# core-debug.net
KiCad netlist of a schematic drawn in EAGLE
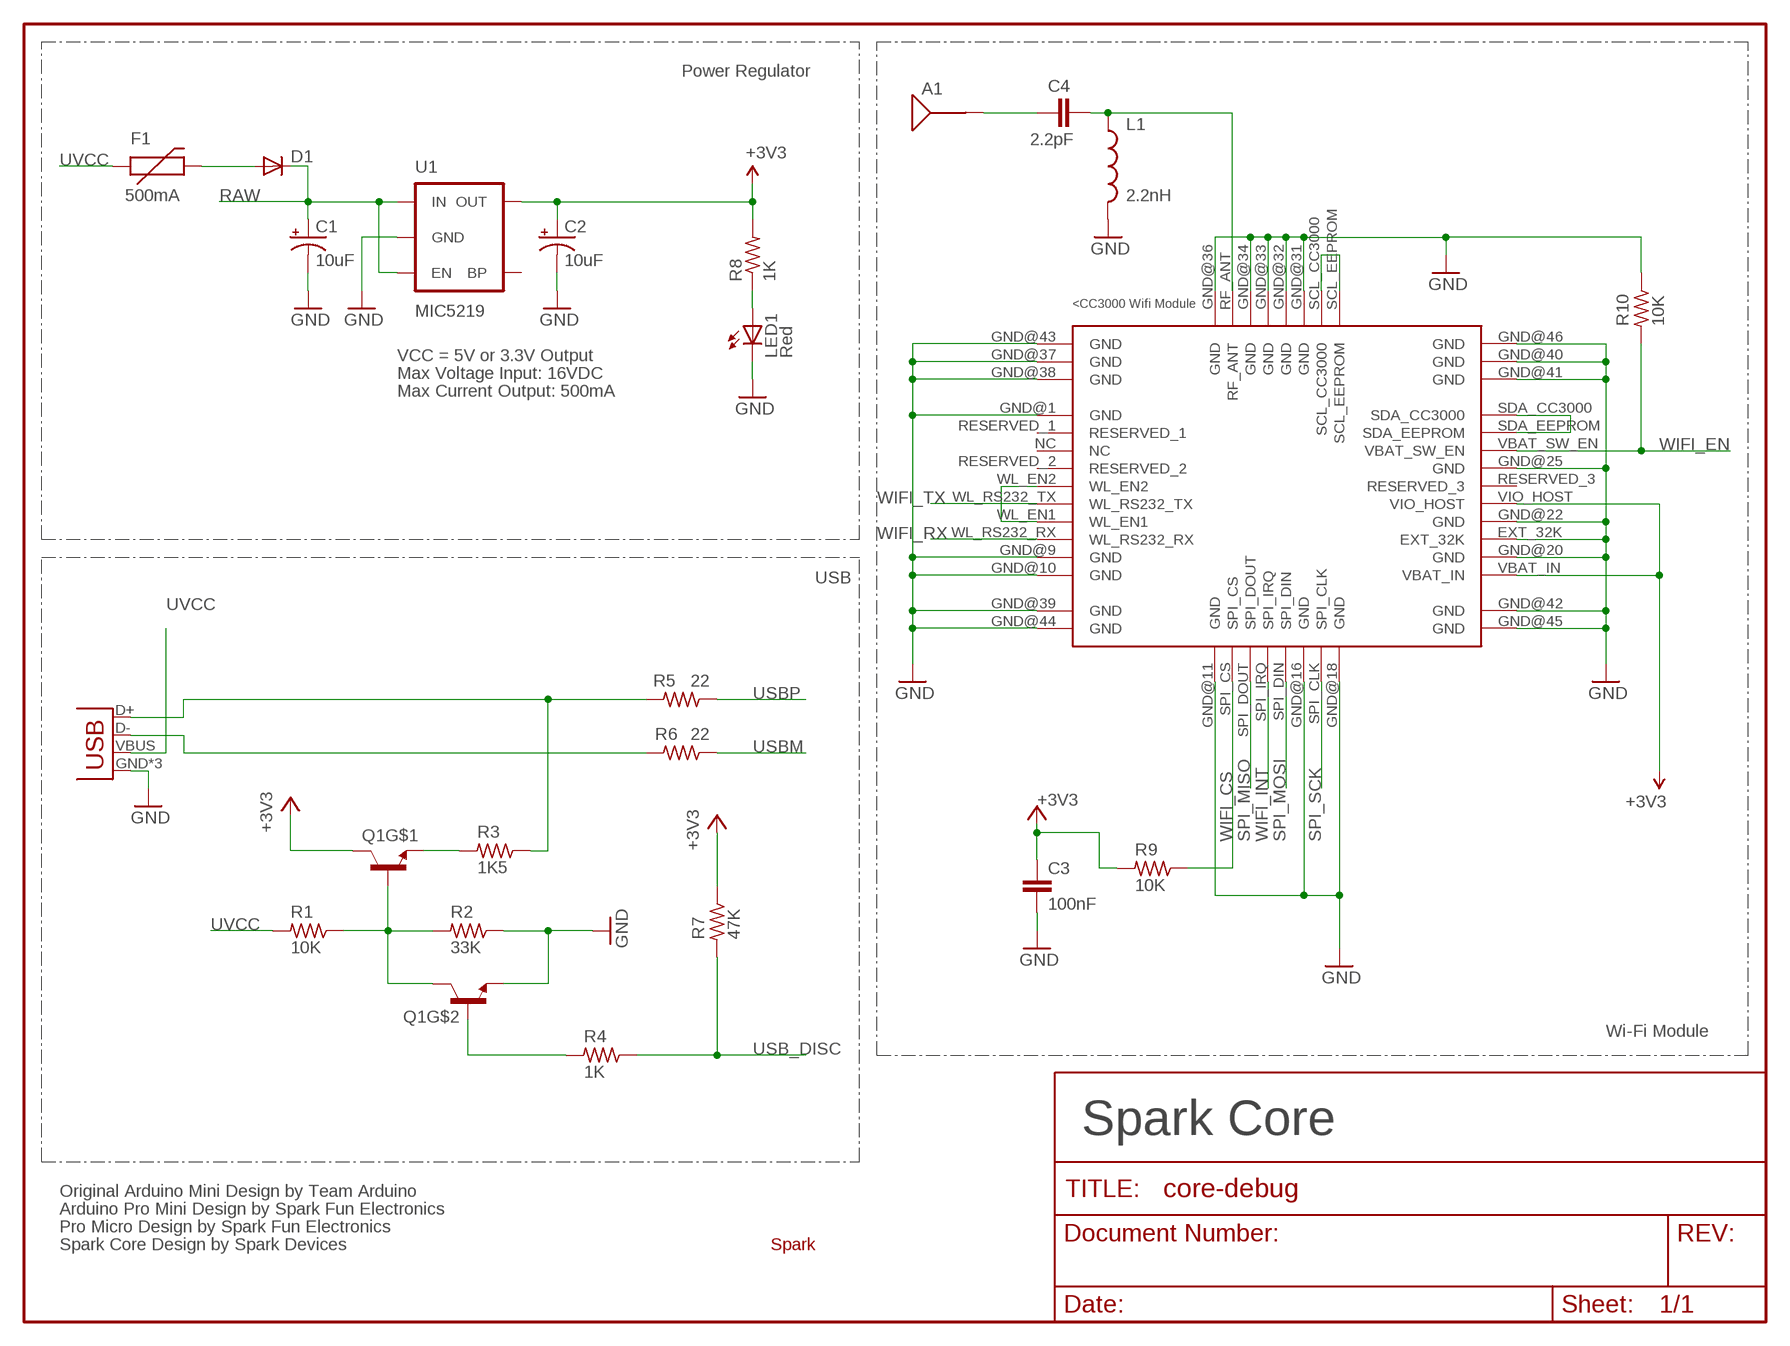
[diagram p0: schematic, sheet 1, part 1 of 2]
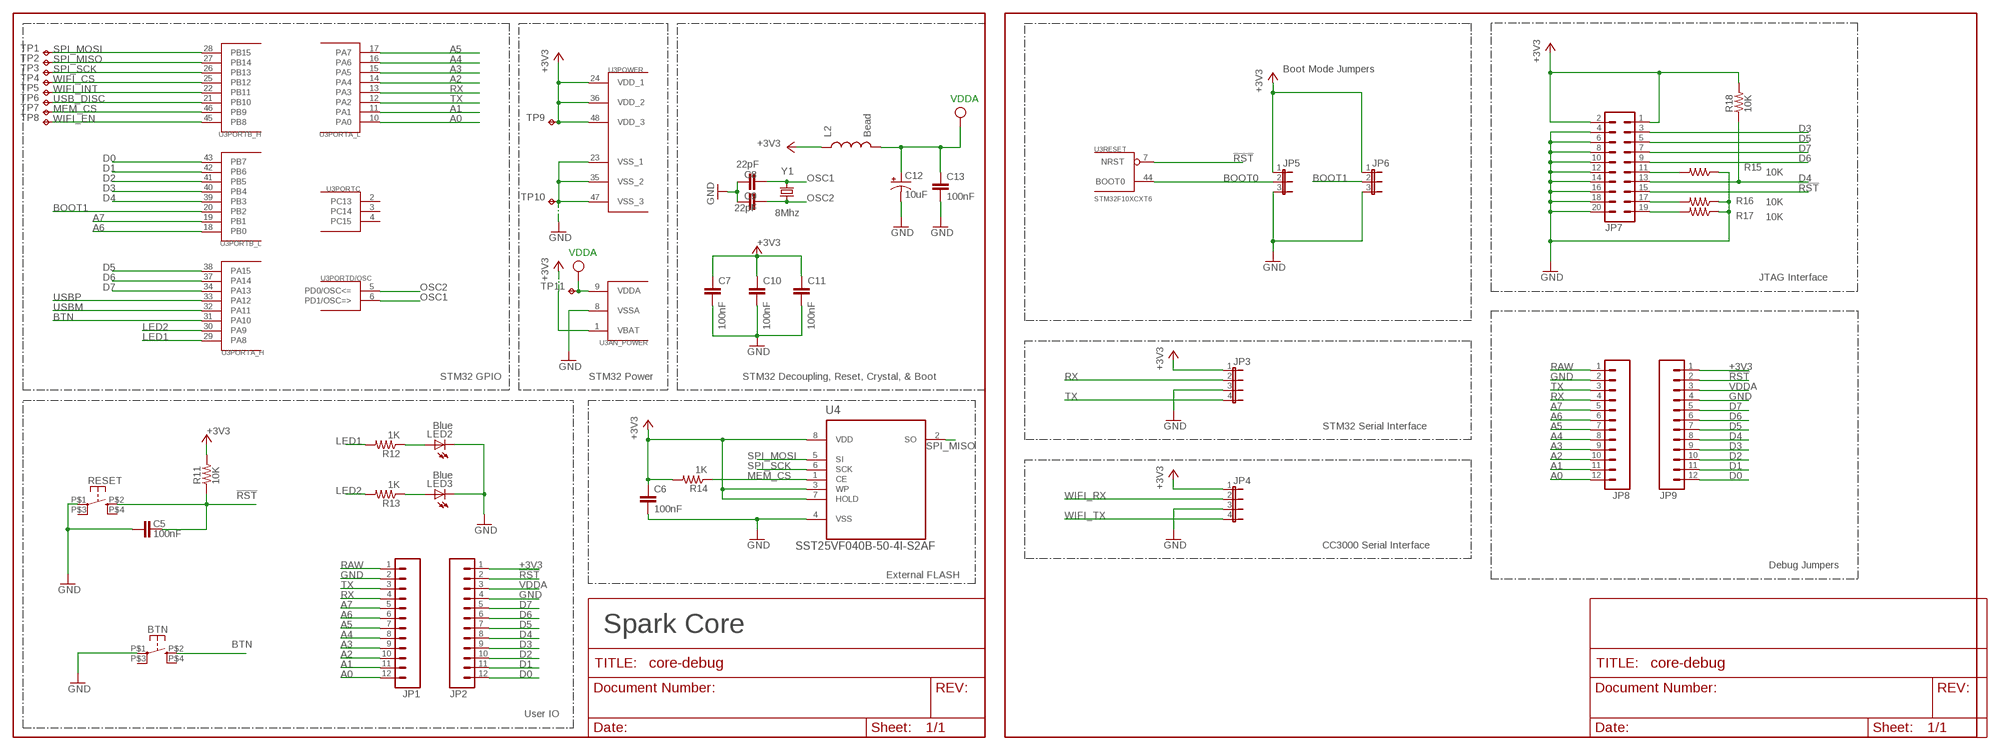
[diagram p1: schematic, sheet 1, part 2 of 2]

(export (version "E")
  (design (tool "Eeschema 10.0.6"))
  (components
    (comp (ref "A1")
      (value "ANTENNA2SMD5")
      (footprint "eagle-import:ANTENNA-CHIP5")
      (libsource (lib "eagle-import") (part "ANTENNA2SMD5"))
    )
    (comp (ref "BTN")
      (value "KMR211GLFS")
      (footprint "eagle-import:PUSHBUTTON-KMR241GLFS")
      (libsource (lib "eagle-import") (part "BUTTON-KMR241GLFS"))
    )
    (comp (ref "C1")
      (value "10uF")
      (footprint "eagle-import:EIA3216")
      (libsource (lib "eagle-import") (part "CAP_POL1206"))
    )
    (comp (ref "C2")
      (value "10uF")
      (footprint "eagle-import:EIA3216")
      (libsource (lib "eagle-import") (part "CAP_POL1206"))
    )
    (comp (ref "C3")
      (value "100nF")
      (footprint "eagle-import:C0603")
      (libsource (lib "eagle-import") (part "C-EUC0603"))
    )
    (comp (ref "C4")
      (value "2.2pF")
      (footprint "eagle-import:C0603")
      (libsource (lib "eagle-import") (part "C-EUC0603"))
    )
    (comp (ref "C5")
      (value "100nF")
      (footprint "eagle-import:C0603")
      (libsource (lib "eagle-import") (part "C-EUC0603"))
    )
    (comp (ref "C6")
      (value "100nF")
      (footprint "eagle-import:C0603")
      (libsource (lib "eagle-import") (part "C-EUC0603"))
    )
    (comp (ref "C7")
      (value "100nF")
      (footprint "eagle-import:C0603")
      (libsource (lib "eagle-import") (part "C-EUC0603"))
    )
    (comp (ref "C8")
      (value "22pF")
      (footprint "eagle-import:C0603")
      (libsource (lib "eagle-import") (part "C-EUC0603"))
    )
    (comp (ref "C9")
      (value "22pF")
      (footprint "eagle-import:C0603")
      (libsource (lib "eagle-import") (part "C-EUC0603"))
    )
    (comp (ref "C10")
      (value "100nF")
      (footprint "eagle-import:C0603")
      (libsource (lib "eagle-import") (part "C-EUC0603"))
    )
    (comp (ref "C11")
      (value "100nF")
      (footprint "eagle-import:C0603")
      (libsource (lib "eagle-import") (part "C-EUC0603"))
    )
    (comp (ref "C12")
      (value "10uF")
      (footprint "eagle-import:EIA3216")
      (libsource (lib "eagle-import") (part "CAP_POL1206"))
    )
    (comp (ref "C13")
      (value "100nF")
      (footprint "eagle-import:C0603")
      (libsource (lib "eagle-import") (part "C-EUC0603"))
    )
    (comp (ref "D1")
      (value "DIODESOD")
      (footprint "eagle-import:SOD-323")
      (libsource (lib "eagle-import") (part "DIODESOD"))
    )
    (comp (ref "F1")
      (value "500mA")
      (footprint "eagle-import:PTC-1206")
      (libsource (lib "eagle-import") (part "PTCSMD"))
    )
    (comp (ref "JP1")
      (value "M12PTH")
      (footprint "eagle-import:1X12")
      (libsource (lib "eagle-import") (part "M12PTH"))
    )
    (comp (ref "JP2")
      (value "M12PTH")
      (footprint "eagle-import:1X12")
      (libsource (lib "eagle-import") (part "M12PTH"))
    )
    (comp (ref "JP3")
      (value "JP4E")
      (footprint "eagle-import:JP4")
      (libsource (lib "eagle-import") (part "JP4E"))
    )
    (comp (ref "JP4")
      (value "JP4E")
      (footprint "eagle-import:JP4")
      (libsource (lib "eagle-import") (part "JP4E"))
    )
    (comp (ref "JP5")
      (value "JP2E")
      (footprint "eagle-import:JP2")
      (libsource (lib "eagle-import") (part "JP2E"))
    )
    (comp (ref "JP6")
      (value "JP2E")
      (footprint "eagle-import:JP2")
      (libsource (lib "eagle-import") (part "JP2E"))
    )
    (comp (ref "JP7")
      (value "ML20")
      (footprint "eagle-import:ML20")
      (libsource (lib "eagle-import") (part "ML20"))
    )
    (comp (ref "JP8")
      (value "M12PTH")
      (footprint "eagle-import:1X12")
      (libsource (lib "eagle-import") (part "M12PTH"))
    )
    (comp (ref "JP9")
      (value "M12PTH")
      (footprint "eagle-import:1X12")
      (libsource (lib "eagle-import") (part "M12PTH"))
    )
    (comp (ref "L1")
      (value "2.2nH")
      (footprint "eagle-import:0603")
      (libsource (lib "eagle-import") (part "INDUCTOR0603"))
    )
    (comp (ref "L2")
      (value "Bead")
      (footprint "eagle-import:0603")
      (libsource (lib "eagle-import") (part "INDUCTOR0603"))
    )
    (comp (ref "LED1")
      (value "Red")
      (footprint "eagle-import:LED-0603")
      (libsource (lib "eagle-import") (part "LED0603"))
    )
    (comp (ref "LED2")
      (value "Blue")
      (footprint "eagle-import:LED-0603")
      (libsource (lib "eagle-import") (part "LED0603"))
    )
    (comp (ref "LED3")
      (value "Blue")
      (footprint "eagle-import:LED-0603")
      (libsource (lib "eagle-import") (part "LED0603"))
    )
    (comp (ref "Q1")
      (value "MMDT3904")
      (footprint "eagle-import:SOT363")
      (libsource (lib "eagle-import") (part "MMDT3904"))
    )
    (comp (ref "R1")
      (value "10K")
      (footprint "eagle-import:R0603")
      (libsource (lib "eagle-import") (part "R-US_R0603"))
    )
    (comp (ref "R2")
      (value "33K")
      (footprint "eagle-import:R0603")
      (libsource (lib "eagle-import") (part "R-US_R0603"))
    )
    (comp (ref "R3")
      (value "1K5")
      (footprint "eagle-import:R0603")
      (libsource (lib "eagle-import") (part "R-US_R0603"))
    )
    (comp (ref "R4")
      (value "1K")
      (footprint "eagle-import:R0603")
      (libsource (lib "eagle-import") (part "R-US_R0603"))
    )
    (comp (ref "R5")
      (value "22")
      (footprint "eagle-import:R0603")
      (libsource (lib "eagle-import") (part "R-US_R0603"))
    )
    (comp (ref "R6")
      (value "22")
      (footprint "eagle-import:R0603")
      (libsource (lib "eagle-import") (part "R-US_R0603"))
    )
    (comp (ref "R7")
      (value "47K")
      (footprint "eagle-import:R0603")
      (libsource (lib "eagle-import") (part "R-US_R0603"))
    )
    (comp (ref "R8")
      (value "1K")
      (footprint "eagle-import:R0603")
      (libsource (lib "eagle-import") (part "R-US_R0603"))
    )
    (comp (ref "R9")
      (value "10K")
      (footprint "eagle-import:R0603")
      (libsource (lib "eagle-import") (part "R-US_R0603"))
    )
    (comp (ref "R10")
      (value "10K")
      (footprint "eagle-import:R0603")
      (libsource (lib "eagle-import") (part "R-US_R0603"))
    )
    (comp (ref "R11")
      (value "10K")
      (footprint "eagle-import:R0603")
      (libsource (lib "eagle-import") (part "R-US_R0603"))
    )
    (comp (ref "R12")
      (value "1K")
      (footprint "eagle-import:R0603")
      (libsource (lib "eagle-import") (part "R-US_R0603"))
    )
    (comp (ref "R13")
      (value "1K")
      (footprint "eagle-import:R0603")
      (libsource (lib "eagle-import") (part "R-US_R0603"))
    )
    (comp (ref "R14")
      (value "1K")
      (footprint "eagle-import:R0603")
      (libsource (lib "eagle-import") (part "R-US_R0603"))
    )
    (comp (ref "R15")
      (value "10K")
      (footprint "eagle-import:R0603")
      (libsource (lib "eagle-import") (part "R-US_R0603"))
    )
    (comp (ref "R16")
      (value "10K")
      (footprint "eagle-import:R0603")
      (libsource (lib "eagle-import") (part "R-US_R0603"))
    )
    (comp (ref "R17")
      (value "10K")
      (footprint "eagle-import:R0603")
      (libsource (lib "eagle-import") (part "R-US_R0603"))
    )
    (comp (ref "R18")
      (value "10K")
      (footprint "eagle-import:R0603")
      (libsource (lib "eagle-import") (part "R-US_R0603"))
    )
    (comp (ref "RESET")
      (value "KMR211GLFS")
      (footprint "eagle-import:PUSHBUTTON-KMR241GLFS")
      (libsource (lib "eagle-import") (part "BUTTON-KMR241GLFS"))
    )
    (comp (ref "TP1")
      (value "TPPAD1-17")
      (footprint "eagle-import:P1-17")
      (libsource (lib "eagle-import") (part "TPPAD1-17"))
    )
    (comp (ref "TP2")
      (value "TPPAD1-17")
      (footprint "eagle-import:P1-17")
      (libsource (lib "eagle-import") (part "TPPAD1-17"))
    )
    (comp (ref "TP3")
      (value "TPPAD1-17")
      (footprint "eagle-import:P1-17")
      (libsource (lib "eagle-import") (part "TPPAD1-17"))
    )
    (comp (ref "TP4")
      (value "TPPAD1-17")
      (footprint "eagle-import:P1-17")
      (libsource (lib "eagle-import") (part "TPPAD1-17"))
    )
    (comp (ref "TP5")
      (value "TPPAD1-17")
      (footprint "eagle-import:P1-17")
      (libsource (lib "eagle-import") (part "TPPAD1-17"))
    )
    (comp (ref "TP6")
      (value "TPPAD1-17")
      (footprint "eagle-import:P1-17")
      (libsource (lib "eagle-import") (part "TPPAD1-17"))
    )
    (comp (ref "TP7")
      (value "TPPAD1-17")
      (footprint "eagle-import:P1-17")
      (libsource (lib "eagle-import") (part "TPPAD1-17"))
    )
    (comp (ref "TP8")
      (value "TPPAD1-17")
      (footprint "eagle-import:P1-17")
      (libsource (lib "eagle-import") (part "TPPAD1-17"))
    )
    (comp (ref "TP9")
      (value "TPPAD1-17")
      (footprint "eagle-import:P1-17")
      (libsource (lib "eagle-import") (part "TPPAD1-17"))
    )
    (comp (ref "TP10")
      (value "TPPAD1-17")
      (footprint "eagle-import:P1-17")
      (libsource (lib "eagle-import") (part "TPPAD1-17"))
    )
    (comp (ref "TP11")
      (value "TPPAD1-17")
      (footprint "eagle-import:P1-17")
      (libsource (lib "eagle-import") (part "TPPAD1-17"))
    )
    (comp (ref "U$1")
      (value "SPARK_LOGO2")
      (footprint "eagle-import:SPARK_LOGO2")
      (libsource (lib "eagle-import") (part "SPARK_LOGO2"))
    )
    (comp (ref "U1")
      (value "MIC5219")
      (footprint "eagle-import:SOT23-5")
      (libsource (lib "eagle-import") (part "V_REG_LDOSMD"))
    )
    (comp (ref "U2")
      (value "CC3000")
      (footprint "eagle-import:CC3000")
      (libsource (lib "eagle-import") (part "CC3000"))
    )
    (comp (ref "U3")
      (value "STM32F10XCXT6")
      (footprint "eagle-import:TQFP48")
      (libsource (lib "eagle-import") (part "STM32F10XCXT6"))
    )
    (comp (ref "U4")
      (value "SST25VF040B-50-4I-S2AF")
      (footprint "eagle-import:SOIC127P790X216-8N")
      (libsource (lib "eagle-import") (part "SST25VF040B-50-4I-S2AF"))
    )
    (comp (ref "X1")
      (value "USB-MICROB")
      (footprint "eagle-import:USB-MICROB")
      (libsource (lib "eagle-import") (part "USB-MICROB"))
    )
    (comp (ref "Y1")
      (value "8Mhz")
      (footprint "eagle-import:CRYSTAL-SMD-5X3")
      (libsource (lib "eagle-import") (part "CRYSTAL5X3"))
    )
  )
  (nets
    (net (code "1") (name "+3V3") (class "Default")
      (node (ref "C10") (pin "1") (pinfunction "1_1") (pintype "passive"))
      (node (ref "C11") (pin "1") (pinfunction "1_1") (pintype "passive"))
      (node (ref "C2") (pin "A") (pinfunction "+_A") (pintype "passive"))
      (node (ref "C3") (pin "1") (pinfunction "1_1") (pintype "passive"))
      (node (ref "C6") (pin "1") (pinfunction "1_1") (pintype "passive"))
      (node (ref "C7") (pin "1") (pinfunction "1_1") (pintype "passive"))
      (node (ref "JP2") (pin "1") (pinfunction "1_1") (pintype "passive"))
      (node (ref "JP3") (pin "1") (pinfunction "1_1") (pintype "passive"))
      (node (ref "JP4") (pin "1") (pinfunction "1_1") (pintype "passive"))
      (node (ref "JP5") (pin "1") (pinfunction "1_1") (pintype "passive"))
      (node (ref "JP6") (pin "1") (pinfunction "1_1") (pintype "passive"))
      (node (ref "JP7") (pin "1") (pinfunction "1_1") (pintype "passive"))
      (node (ref "JP7") (pin "2") (pinfunction "2_2") (pintype "passive"))
      (node (ref "JP9") (pin "1") (pinfunction "1_1") (pintype "passive"))
      (node (ref "L2") (pin "1") (pinfunction "1_1") (pintype "passive"))
      (node (ref "Q1") (pin "3") (pinfunction "C_3") (pintype "passive"))
      (node (ref "R11") (pin "2") (pinfunction "2_2") (pintype "passive"))
      (node (ref "R14") (pin "2") (pinfunction "2_2") (pintype "passive"))
      (node (ref "R18") (pin "2") (pinfunction "2_2") (pintype "passive"))
      (node (ref "R7") (pin "1") (pinfunction "1_1") (pintype "passive"))
      (node (ref "R8") (pin "2") (pinfunction "2_2") (pintype "passive"))
      (node (ref "R9") (pin "2") (pinfunction "2_2") (pintype "passive"))
      (node (ref "TP9") (pin "TP") (pinfunction "TP_TP") (pintype "input"))
      (node (ref "U1") (pin "5") (pinfunction "OUT_5") (pintype "passive"))
      (node (ref "U2") (pin "VBAT_IN") (pinfunction "VBAT_IN_VBAT_IN") (pintype "power_in"))
      (node (ref "U2") (pin "VIO_HOST") (pinfunction "VIO_HOST_VIO_HOST") (pintype "power_in"))
      (node (ref "U3") (pin "1") (pinfunction "VBAT_1") (pintype "power_in"))
      (node (ref "U3") (pin "24") (pinfunction "VDD_1_24") (pintype "power_in"))
      (node (ref "U3") (pin "36") (pinfunction "VDD_2_36") (pintype "power_in"))
      (node (ref "U3") (pin "48") (pinfunction "VDD_3_48") (pintype "power_in"))
      (node (ref "U4") (pin "3") (pinfunction "WP_3") (pintype "input"))
      (node (ref "U4") (pin "7") (pinfunction "HOLD_7") (pintype "input"))
      (node (ref "U4") (pin "8") (pinfunction "VDD_8") (pintype "power_in"))
    )
    (net (code "2") (name "/A0") (class "Default")
      (node (ref "JP1") (pin "12") (pinfunction "12_12") (pintype "passive"))
      (node (ref "JP8") (pin "12") (pinfunction "12_12") (pintype "passive"))
      (node (ref "U3") (pin "10") (pinfunction "PA0_10") (pintype "bidirectional"))
    )
    (net (code "3") (name "/A1") (class "Default")
      (node (ref "JP1") (pin "11") (pinfunction "11_11") (pintype "passive"))
      (node (ref "JP8") (pin "11") (pinfunction "11_11") (pintype "passive"))
      (node (ref "U3") (pin "11") (pinfunction "PA1_11") (pintype "bidirectional"))
    )
    (net (code "4") (name "/A2") (class "Default")
      (node (ref "JP1") (pin "10") (pinfunction "10_10") (pintype "passive"))
      (node (ref "JP8") (pin "10") (pinfunction "10_10") (pintype "passive"))
      (node (ref "U3") (pin "14") (pinfunction "PA4_14") (pintype "bidirectional"))
    )
    (net (code "5") (name "/A3") (class "Default")
      (node (ref "JP1") (pin "9") (pinfunction "9_9") (pintype "passive"))
      (node (ref "JP8") (pin "9") (pinfunction "9_9") (pintype "passive"))
      (node (ref "U3") (pin "15") (pinfunction "PA5_15") (pintype "bidirectional"))
    )
    (net (code "6") (name "/A4") (class "Default")
      (node (ref "JP1") (pin "8") (pinfunction "8_8") (pintype "passive"))
      (node (ref "JP8") (pin "8") (pinfunction "8_8") (pintype "passive"))
      (node (ref "U3") (pin "16") (pinfunction "PA6_16") (pintype "bidirectional"))
    )
    (net (code "7") (name "/A5") (class "Default")
      (node (ref "JP1") (pin "7") (pinfunction "7_7") (pintype "passive"))
      (node (ref "JP8") (pin "7") (pinfunction "7_7") (pintype "passive"))
      (node (ref "U3") (pin "17") (pinfunction "PA7_17") (pintype "bidirectional"))
    )
    (net (code "8") (name "/A6") (class "Default")
      (node (ref "JP1") (pin "6") (pinfunction "6_6") (pintype "passive"))
      (node (ref "JP8") (pin "6") (pinfunction "6_6") (pintype "passive"))
      (node (ref "U3") (pin "18") (pinfunction "PB0_18") (pintype "bidirectional"))
    )
    (net (code "9") (name "/A7") (class "Default")
      (node (ref "JP1") (pin "5") (pinfunction "5_5") (pintype "passive"))
      (node (ref "JP8") (pin "5") (pinfunction "5_5") (pintype "passive"))
      (node (ref "U3") (pin "19") (pinfunction "PB1_19") (pintype "bidirectional"))
    )
    (net (code "10") (name "/BOOT0") (class "Default")
      (node (ref "JP5") (pin "2") (pinfunction "2_2") (pintype "passive"))
      (node (ref "U3") (pin "44") (pinfunction "BOOT0_44") (pintype "input"))
    )
    (net (code "11") (name "/BOOT1") (class "Default")
      (node (ref "JP6") (pin "2") (pinfunction "2_2") (pintype "passive"))
      (node (ref "U3") (pin "20") (pinfunction "PB2_20") (pintype "bidirectional"))
    )
    (net (code "12") (name "/BTN") (class "Default")
      (node (ref "BTN") (pin "P$2") (pinfunction "2_P$2") (pintype "passive"))
      (node (ref "U3") (pin "31") (pinfunction "PA10_31") (pintype "bidirectional"))
    )
    (net (code "13") (name "/D0") (class "Default")
      (node (ref "JP2") (pin "12") (pinfunction "12_12") (pintype "passive"))
      (node (ref "JP9") (pin "12") (pinfunction "12_12") (pintype "passive"))
      (node (ref "U3") (pin "43") (pinfunction "PB7_43") (pintype "bidirectional"))
    )
    (net (code "14") (name "/D1") (class "Default")
      (node (ref "JP2") (pin "11") (pinfunction "11_11") (pintype "passive"))
      (node (ref "JP9") (pin "11") (pinfunction "11_11") (pintype "passive"))
      (node (ref "U3") (pin "42") (pinfunction "PB6_42") (pintype "bidirectional"))
    )
    (net (code "15") (name "/D2") (class "Default")
      (node (ref "JP2") (pin "10") (pinfunction "10_10") (pintype "passive"))
      (node (ref "JP9") (pin "10") (pinfunction "10_10") (pintype "passive"))
      (node (ref "U3") (pin "41") (pinfunction "PB5_41") (pintype "bidirectional"))
    )
    (net (code "16") (name "/D3") (class "Default")
      (node (ref "JP2") (pin "9") (pinfunction "9_9") (pintype "passive"))
      (node (ref "JP7") (pin "3") (pinfunction "3_3") (pintype "passive"))
      (node (ref "JP9") (pin "9") (pinfunction "9_9") (pintype "passive"))
      (node (ref "U3") (pin "40") (pinfunction "PB4_40") (pintype "bidirectional"))
    )
    (net (code "17") (name "/D4") (class "Default")
      (node (ref "JP2") (pin "8") (pinfunction "8_8") (pintype "passive"))
      (node (ref "JP7") (pin "13") (pinfunction "13_13") (pintype "passive"))
      (node (ref "JP9") (pin "8") (pinfunction "8_8") (pintype "passive"))
      (node (ref "R18") (pin "1") (pinfunction "1_1") (pintype "passive"))
      (node (ref "U3") (pin "39") (pinfunction "PB3_39") (pintype "bidirectional"))
    )
    (net (code "18") (name "/D5") (class "Default")
      (node (ref "JP2") (pin "7") (pinfunction "7_7") (pintype "passive"))
      (node (ref "JP7") (pin "5") (pinfunction "5_5") (pintype "passive"))
      (node (ref "JP9") (pin "7") (pinfunction "7_7") (pintype "passive"))
      (node (ref "U3") (pin "38") (pinfunction "PA15_38") (pintype "bidirectional"))
    )
    (net (code "19") (name "/D6") (class "Default")
      (node (ref "JP2") (pin "6") (pinfunction "6_6") (pintype "passive"))
      (node (ref "JP7") (pin "9") (pinfunction "9_9") (pintype "passive"))
      (node (ref "JP9") (pin "6") (pinfunction "6_6") (pintype "passive"))
      (node (ref "U3") (pin "37") (pinfunction "PA14_37") (pintype "bidirectional"))
    )
    (net (code "20") (name "/D7") (class "Default")
      (node (ref "JP2") (pin "5") (pinfunction "5_5") (pintype "passive"))
      (node (ref "JP7") (pin "7") (pinfunction "7_7") (pintype "passive"))
      (node (ref "JP9") (pin "5") (pinfunction "5_5") (pintype "passive"))
      (node (ref "U3") (pin "34") (pinfunction "PA13_34") (pintype "bidirectional"))
    )
    (net (code "21") (name "/LED1") (class "Default")
      (node (ref "R12") (pin "2") (pinfunction "2_2") (pintype "passive"))
      (node (ref "U3") (pin "29") (pinfunction "PA8_29") (pintype "bidirectional"))
    )
    (net (code "22") (name "/LED2") (class "Default")
      (node (ref "R13") (pin "2") (pinfunction "2_2") (pintype "passive"))
      (node (ref "U3") (pin "30") (pinfunction "PA9_30") (pintype "bidirectional"))
    )
    (net (code "23") (name "/MEM_CS") (class "Default")
      (node (ref "R14") (pin "1") (pinfunction "1_1") (pintype "passive"))
      (node (ref "TP7") (pin "TP") (pinfunction "TP_TP") (pintype "input"))
      (node (ref "U3") (pin "46") (pinfunction "PB9_46") (pintype "bidirectional"))
      (node (ref "U4") (pin "1") (pinfunction "CE_1") (pintype "input"))
    )
    (net (code "24") (name "/OSC1") (class "Default")
      (node (ref "C8") (pin "1") (pinfunction "1_1") (pintype "passive"))
      (node (ref "U3") (pin "6") (pinfunction "PD1/OSC=>_6") (pintype "bidirectional"))
      (node (ref "Y1") (pin "3") (pinfunction "2_3") (pintype "passive"))
    )
    (net (code "25") (name "/OSC2") (class "Default")
      (node (ref "C9") (pin "1") (pinfunction "1_1") (pintype "passive"))
      (node (ref "U3") (pin "5") (pinfunction "PD0/OSC<=_5") (pintype "bidirectional"))
      (node (ref "Y1") (pin "1") (pinfunction "1_1") (pintype "passive"))
    )
    (net (code "26") (name "/RAW") (class "Default")
      (node (ref "C1") (pin "A") (pinfunction "+_A") (pintype "passive"))
      (node (ref "D1") (pin "1") (pinfunction "C_1") (pintype "passive"))
      (node (ref "JP1") (pin "1") (pinfunction "1_1") (pintype "passive"))
      (node (ref "JP8") (pin "1") (pinfunction "1_1") (pintype "passive"))
      (node (ref "U1") (pin "1") (pinfunction "IN_1") (pintype "input"))
      (node (ref "U1") (pin "3") (pinfunction "EN_3") (pintype "input"))
    )
    (net (code "27") (name "/RX") (class "Default")
      (node (ref "JP1") (pin "4") (pinfunction "4_4") (pintype "passive"))
      (node (ref "JP3") (pin "2") (pinfunction "2_2") (pintype "passive"))
      (node (ref "JP8") (pin "4") (pinfunction "4_4") (pintype "passive"))
      (node (ref "U3") (pin "13") (pinfunction "PA3_13") (pintype "bidirectional"))
    )
    (net (code "28") (name "/SPI_MISO") (class "Default")
      (node (ref "TP2") (pin "TP") (pinfunction "TP_TP") (pintype "input"))
      (node (ref "U2") (pin "SPI_DOUT") (pinfunction "SPI_DOUT_SPI_DOUT") (pintype "output"))
      (node (ref "U3") (pin "27") (pinfunction "PB14_27") (pintype "bidirectional"))
      (node (ref "U4") (pin "2") (pinfunction "SO_2") (pintype "output"))
    )
    (net (code "29") (name "/SPI_MOSI") (class "Default")
      (node (ref "TP1") (pin "TP") (pinfunction "TP_TP") (pintype "input"))
      (node (ref "U2") (pin "SPI_DIN") (pinfunction "SPI_DIN_SPI_DIN") (pintype "input"))
      (node (ref "U3") (pin "28") (pinfunction "PB15_28") (pintype "bidirectional"))
      (node (ref "U4") (pin "5") (pinfunction "SI_5") (pintype "input"))
    )
    (net (code "30") (name "/SPI_SCK") (class "Default")
      (node (ref "TP3") (pin "TP") (pinfunction "TP_TP") (pintype "input"))
      (node (ref "U2") (pin "SPI_CLK") (pinfunction "SPI_CLK_SPI_CLK") (pintype "input"))
      (node (ref "U3") (pin "26") (pinfunction "PB13_26") (pintype "bidirectional"))
      (node (ref "U4") (pin "6") (pinfunction "SCK_6") (pintype "input"))
    )
    (net (code "31") (name "/TX") (class "Default")
      (node (ref "JP1") (pin "3") (pinfunction "3_3") (pintype "passive"))
      (node (ref "JP3") (pin "4") (pinfunction "4_4") (pintype "passive"))
      (node (ref "JP8") (pin "3") (pinfunction "3_3") (pintype "passive"))
      (node (ref "U3") (pin "12") (pinfunction "PA2_12") (pintype "bidirectional"))
    )
    (net (code "32") (name "/USBM") (class "Default")
      (node (ref "R6") (pin "1") (pinfunction "1_1") (pintype "passive"))
      (node (ref "U3") (pin "32") (pinfunction "PA11_32") (pintype "bidirectional"))
    )
    (net (code "33") (name "/USBP") (class "Default")
      (node (ref "R5") (pin "1") (pinfunction "1_1") (pintype "passive"))
      (node (ref "U3") (pin "33") (pinfunction "PA12_33") (pintype "bidirectional"))
    )
    (net (code "34") (name "/USB_DISC") (class "Default")
      (node (ref "R4") (pin "1") (pinfunction "1_1") (pintype "passive"))
      (node (ref "R7") (pin "2") (pinfunction "2_2") (pintype "passive"))
      (node (ref "TP6") (pin "TP") (pinfunction "TP_TP") (pintype "input"))
      (node (ref "U3") (pin "21") (pinfunction "PB10_21") (pintype "bidirectional"))
    )
    (net (code "35") (name "/UVCC") (class "Default")
      (node (ref "F1") (pin "1") (pinfunction "1_1") (pintype "bidirectional"))
      (node (ref "R1") (pin "2") (pinfunction "2_2") (pintype "passive"))
      (node (ref "X1") (pin "VBUS") (pinfunction "VBUS_VBUS") (pintype "bidirectional"))
    )
    (net (code "36") (name "/WIFI_CS") (class "Default")
      (node (ref "R9") (pin "1") (pinfunction "1_1") (pintype "passive"))
      (node (ref "TP4") (pin "TP") (pinfunction "TP_TP") (pintype "input"))
      (node (ref "U2") (pin "SPI_CS") (pinfunction "SPI_CS_SPI_CS") (pintype "input"))
      (node (ref "U3") (pin "25") (pinfunction "PB12_25") (pintype "bidirectional"))
    )
    (net (code "37") (name "/WIFI_EN") (class "Default")
      (node (ref "R10") (pin "2") (pinfunction "2_2") (pintype "passive"))
      (node (ref "TP8") (pin "TP") (pinfunction "TP_TP") (pintype "input"))
      (node (ref "U2") (pin "VBAT_SW_EN") (pinfunction "VBAT_SW_EN_VBAT_SW_EN") (pintype "input"))
      (node (ref "U3") (pin "45") (pinfunction "PB8_45") (pintype "bidirectional"))
    )
    (net (code "38") (name "/WIFI_INT") (class "Default")
      (node (ref "TP5") (pin "TP") (pinfunction "TP_TP") (pintype "input"))
      (node (ref "U2") (pin "SPI_IRQ") (pinfunction "SPI_IRQ_SPI_IRQ") (pintype "output"))
      (node (ref "U3") (pin "22") (pinfunction "PB11_22") (pintype "bidirectional"))
    )
    (net (code "39") (name "/WIFI_RX") (class "Default")
      (node (ref "JP4") (pin "2") (pinfunction "2_2") (pintype "passive"))
      (node (ref "U2") (pin "WL_RS232_RX") (pinfunction "WL_RS232_RX_WL_RS232_RX") (pintype "input"))
    )
    (net (code "40") (name "/WIFI_TX") (class "Default")
      (node (ref "JP4") (pin "4") (pinfunction "4_4") (pintype "passive"))
      (node (ref "U2") (pin "WL_RS232_TX") (pinfunction "WL_RS232_TX_WL_RS232_TX") (pintype "output"))
    )
    (net (code "41") (name "/~{RST}") (class "Default")
      (node (ref "C5") (pin "2") (pinfunction "2_2") (pintype "passive"))
      (node (ref "JP2") (pin "2") (pinfunction "2_2") (pintype "passive"))
      (node (ref "JP7") (pin "15") (pinfunction "15_15") (pintype "passive"))
      (node (ref "JP9") (pin "2") (pinfunction "2_2") (pintype "passive"))
      (node (ref "R11") (pin "1") (pinfunction "1_1") (pintype "passive"))
      (node (ref "RESET") (pin "P$2") (pinfunction "2_P$2") (pintype "passive"))
      (node (ref "U3") (pin "7") (pinfunction "NRST_7") (pintype "input"))
    )
    (net (code "42") (name "GND") (class "Default")
      (node (ref "BTN") (pin "P$1") (pinfunction "1_P$1") (pintype "passive"))
      (node (ref "C1") (pin "C") (pinfunction "-_C") (pintype "passive"))
      (node (ref "C10") (pin "2") (pinfunction "2_2") (pintype "passive"))
      (node (ref "C11") (pin "2") (pinfunction "2_2") (pintype "passive"))
      (node (ref "C12") (pin "C") (pinfunction "-_C") (pintype "passive"))
      (node (ref "C13") (pin "2") (pinfunction "2_2") (pintype "passive"))
      (node (ref "C2") (pin "C") (pinfunction "-_C") (pintype "passive"))
      (node (ref "C3") (pin "2") (pinfunction "2_2") (pintype "passive"))
      (node (ref "C5") (pin "1") (pinfunction "1_1") (pintype "passive"))
      (node (ref "C6") (pin "2") (pinfunction "2_2") (pintype "passive"))
      (node (ref "C7") (pin "2") (pinfunction "2_2") (pintype "passive"))
      (node (ref "C8") (pin "2") (pinfunction "2_2") (pintype "passive"))
      (node (ref "C9") (pin "2") (pinfunction "2_2") (pintype "passive"))
      (node (ref "JP1") (pin "2") (pinfunction "2_2") (pintype "passive"))
      (node (ref "JP2") (pin "4") (pinfunction "4_4") (pintype "passive"))
      (node (ref "JP3") (pin "3") (pinfunction "3_3") (pintype "passive"))
      (node (ref "JP4") (pin "3") (pinfunction "3_3") (pintype "passive"))
      (node (ref "JP5") (pin "3") (pinfunction "3_3") (pintype "passive"))
      (node (ref "JP6") (pin "3") (pinfunction "3_3") (pintype "passive"))
      (node (ref "JP7") (pin "10") (pinfunction "10_10") (pintype "passive"))
      (node (ref "JP7") (pin "12") (pinfunction "12_12") (pintype "passive"))
      (node (ref "JP7") (pin "14") (pinfunction "14_14") (pintype "passive"))
      (node (ref "JP7") (pin "16") (pinfunction "16_16") (pintype "passive"))
      (node (ref "JP7") (pin "18") (pinfunction "18_18") (pintype "passive"))
      (node (ref "JP7") (pin "20") (pinfunction "20_20") (pintype "passive"))
      (node (ref "JP7") (pin "4") (pinfunction "4_4") (pintype "passive"))
      (node (ref "JP7") (pin "6") (pinfunction "6_6") (pintype "passive"))
      (node (ref "JP7") (pin "8") (pinfunction "8_8") (pintype "passive"))
      (node (ref "JP8") (pin "2") (pinfunction "2_2") (pintype "passive"))
      (node (ref "JP9") (pin "4") (pinfunction "4_4") (pintype "passive"))
      (node (ref "L1") (pin "2") (pinfunction "2_2") (pintype "passive"))
      (node (ref "LED1") (pin "C") (pinfunction "C_C") (pintype "passive"))
      (node (ref "LED2") (pin "C") (pinfunction "C_C") (pintype "passive"))
      (node (ref "LED3") (pin "C") (pinfunction "C_C") (pintype "passive"))
      (node (ref "Q1") (pin "1") (pinfunction "E_1") (pintype "passive"))
      (node (ref "R10") (pin "1") (pinfunction "1_1") (pintype "passive"))
      (node (ref "R15") (pin "1") (pinfunction "1_1") (pintype "passive"))
      (node (ref "R16") (pin "1") (pinfunction "1_1") (pintype "passive"))
      (node (ref "R17") (pin "1") (pinfunction "1_1") (pintype "passive"))
      (node (ref "R2") (pin "1") (pinfunction "1_1") (pintype "passive"))
      (node (ref "RESET") (pin "P$1") (pinfunction "1_P$1") (pintype "passive"))
      (node (ref "TP10") (pin "TP") (pinfunction "TP_TP") (pintype "input"))
      (node (ref "U1") (pin "2") (pinfunction "GND_2") (pintype "input"))
      (node (ref "U2") (pin "EXT_32K") (pinfunction "EXT_32K_EXT_32K") (pintype "bidirectional"))
      (node (ref "U2") (pin "GND@1") (pinfunction "GND_GND@1") (pintype "power_in"))
      (node (ref "U2") (pin "GND@10") (pinfunction "GND_GND@10") (pintype "power_in"))
      (node (ref "U2") (pin "GND@11") (pinfunction "GND_GND@11") (pintype "power_in"))
      (node (ref "U2") (pin "GND@16") (pinfunction "GND_GND@16") (pintype "power_in"))
      (node (ref "U2") (pin "GND@18") (pinfunction "GND_GND@18") (pintype "power_in"))
      (node (ref "U2") (pin "GND@20") (pinfunction "GND_GND@20") (pintype "power_in"))
      (node (ref "U2") (pin "GND@22") (pinfunction "GND_GND@22") (pintype "power_in"))
      (node (ref "U2") (pin "GND@25") (pinfunction "GND_GND@25") (pintype "power_in"))
      (node (ref "U2") (pin "GND@31") (pinfunction "GND_GND@31") (pintype "power_in"))
      (node (ref "U2") (pin "GND@32") (pinfunction "GND_GND@32") (pintype "power_in"))
      (node (ref "U2") (pin "GND@33") (pinfunction "GND_GND@33") (pintype "power_in"))
      (node (ref "U2") (pin "GND@34") (pinfunction "GND_GND@34") (pintype "power_in"))
      (node (ref "U2") (pin "GND@36") (pinfunction "GND_GND@36") (pintype "power_in"))
      (node (ref "U2") (pin "GND@37") (pinfunction "GND_GND@37") (pintype "power_in"))
      (node (ref "U2") (pin "GND@38") (pinfunction "GND_GND@38") (pintype "power_in"))
      (node (ref "U2") (pin "GND@39") (pinfunction "GND_GND@39") (pintype "power_in"))
      (node (ref "U2") (pin "GND@40") (pinfunction "GND_GND@40") (pintype "power_in"))
      (node (ref "U2") (pin "GND@41") (pinfunction "GND_GND@41") (pintype "power_in"))
      (node (ref "U2") (pin "GND@42") (pinfunction "GND_GND@42") (pintype "power_in"))
      (node (ref "U2") (pin "GND@43") (pinfunction "GND_GND@43") (pintype "power_in"))
      (node (ref "U2") (pin "GND@44") (pinfunction "GND_GND@44") (pintype "power_in"))
      (node (ref "U2") (pin "GND@45") (pinfunction "GND_GND@45") (pintype "power_in"))
      (node (ref "U2") (pin "GND@46") (pinfunction "GND_GND@46") (pintype "power_in"))
      (node (ref "U2") (pin "GND@9") (pinfunction "GND_GND@9") (pintype "power_in"))
      (node (ref "U3") (pin "23") (pinfunction "VSS_1_23") (pintype "power_in"))
      (node (ref "U3") (pin "35") (pinfunction "VSS_2_35") (pintype "power_in"))
      (node (ref "U3") (pin "47") (pinfunction "VSS_3_47") (pintype "power_in"))
      (node (ref "U3") (pin "8") (pinfunction "VSSA_8") (pintype "power_in"))
      (node (ref "U4") (pin "4") (pinfunction "VSS_4") (pintype "passive"))
      (node (ref "X1") (pin "GND") (pinfunction "GND_GND") (pintype "bidirectional"))
      (node (ref "X1") (pin "MT1") (pinfunction "GND_MT1") (pintype "bidirectional"))
      (node (ref "X1") (pin "MT2") (pinfunction "GND_MT2") (pintype "bidirectional"))
    )
    (net (code "43") (name "Net-(A1-SIGNAL)") (class "Default")
      (node (ref "A1") (pin "FEED") (pinfunction "SIGNAL_FEED") (pintype "bidirectional"))
      (node (ref "C4") (pin "1") (pinfunction "1_1") (pintype "passive"))
    )
    (net (code "44") (name "Net-(C4-Pad2)") (class "Default")
      (node (ref "C4") (pin "2") (pinfunction "2_2") (pintype "passive"))
      (node (ref "L1") (pin "1") (pinfunction "1_1") (pintype "passive"))
      (node (ref "U2") (pin "RF_ANT") (pinfunction "RF_ANT_RF_ANT") (pintype "bidirectional"))
    )
    (net (code "45") (name "Net-(D1-A)") (class "Default")
      (node (ref "D1") (pin "2") (pinfunction "A_2") (pintype "passive"))
      (node (ref "F1") (pin "2") (pinfunction "2_2") (pintype "bidirectional"))
    )
    (net (code "46") (name "Net-(JP7-Pad11)") (class "Default")
      (node (ref "JP7") (pin "11") (pinfunction "11_11") (pintype "passive"))
      (node (ref "R15") (pin "2") (pinfunction "2_2") (pintype "passive"))
    )
    (net (code "47") (name "Net-(JP7-Pad17)") (class "Default")
      (node (ref "JP7") (pin "17") (pinfunction "17_17") (pintype "passive"))
      (node (ref "R16") (pin "2") (pinfunction "2_2") (pintype "passive"))
    )
    (net (code "48") (name "Net-(JP7-Pad19)") (class "Default")
      (node (ref "JP7") (pin "19") (pinfunction "19_19") (pintype "passive"))
      (node (ref "R17") (pin "2") (pinfunction "2_2") (pintype "passive"))
    )
    (net (code "49") (name "Net-(LED1-PadA)") (class "Default")
      (node (ref "LED1") (pin "A") (pinfunction "A_A") (pintype "passive"))
      (node (ref "R8") (pin "1") (pinfunction "1_1") (pintype "passive"))
    )
    (net (code "50") (name "Net-(LED2-PadA)") (class "Default")
      (node (ref "LED2") (pin "A") (pinfunction "A_A") (pintype "passive"))
      (node (ref "R12") (pin "1") (pinfunction "1_1") (pintype "passive"))
    )
    (net (code "51") (name "Net-(LED3-PadA)") (class "Default")
      (node (ref "LED3") (pin "A") (pinfunction "A_A") (pintype "passive"))
      (node (ref "R13") (pin "1") (pinfunction "1_1") (pintype "passive"))
    )
    (net (code "52") (name "Net-(Q1A-B)") (class "Default")
      (node (ref "Q1") (pin "5") (pinfunction "B_5") (pintype "passive"))
      (node (ref "Q1") (pin "6") (pinfunction "C_6") (pintype "passive"))
      (node (ref "R1") (pin "1") (pinfunction "1_1") (pintype "passive"))
      (node (ref "R2") (pin "2") (pinfunction "2_2") (pintype "passive"))
    )
    (net (code "53") (name "Net-(Q1A-E)") (class "Default")
      (node (ref "Q1") (pin "4") (pinfunction "E_4") (pintype "passive"))
      (node (ref "R3") (pin "2") (pinfunction "2_2") (pintype "passive"))
    )
    (net (code "54") (name "Net-(Q1B-B)") (class "Default")
      (node (ref "Q1") (pin "2") (pinfunction "B_2") (pintype "passive"))
      (node (ref "R4") (pin "2") (pinfunction "2_2") (pintype "passive"))
    )
    (net (code "55") (name "Net-(R3-Pad1)") (class "Default")
      (node (ref "R3") (pin "1") (pinfunction "1_1") (pintype "passive"))
      (node (ref "R5") (pin "2") (pinfunction "2_2") (pintype "passive"))
      (node (ref "X1") (pin "D+") (pinfunction "D+_D+") (pintype "bidirectional"))
    )
    (net (code "56") (name "Net-(R6-Pad2)") (class "Default")
      (node (ref "R6") (pin "2") (pinfunction "2_2") (pintype "passive"))
      (node (ref "X1") (pin "D-") (pinfunction "D-_D-") (pintype "bidirectional"))
    )
    (net (code "57") (name "Net-(U2-PadSCL_CC3000)") (class "Default")
      (node (ref "U2") (pin "SCL_CC3000") (pinfunction "SCL_CC3000_SCL_CC3000") (pintype "bidirectional"))
      (node (ref "U2") (pin "SCL_EEPROM") (pinfunction "SCL_EEPROM_SCL_EEPROM") (pintype "bidirectional"))
    )
    (net (code "58") (name "Net-(U2-PadSDA_CC3000)") (class "Default")
      (node (ref "U2") (pin "SDA_CC3000") (pinfunction "SDA_CC3000_SDA_CC3000") (pintype "bidirectional"))
      (node (ref "U2") (pin "SDA_EEPROM") (pinfunction "SDA_EEPROM_SDA_EEPROM") (pintype "bidirectional"))
    )
    (net (code "59") (name "Net-(U2-PadWL_EN1)") (class "Default")
      (node (ref "U2") (pin "WL_EN1") (pinfunction "WL_EN1_WL_EN1") (pintype "input"))
      (node (ref "U2") (pin "WL_EN2") (pinfunction "WL_EN2_WL_EN2") (pintype "input"))
    )
    (net (code "60") (name "VCC") (class "Default")
      (node (ref "C12") (pin "A") (pinfunction "+_A") (pintype "passive"))
      (node (ref "C13") (pin "1") (pinfunction "1_1") (pintype "passive"))
      (node (ref "JP2") (pin "3") (pinfunction "3_3") (pintype "passive"))
      (node (ref "JP9") (pin "3") (pinfunction "3_3") (pintype "passive"))
      (node (ref "L2") (pin "2") (pinfunction "2_2") (pintype "passive"))
      (node (ref "TP11") (pin "TP") (pinfunction "TP_TP") (pintype "input"))
      (node (ref "U3") (pin "9") (pinfunction "VDDA_9") (pintype "power_in"))
    )
    (net (code "61") (name "unconnected-(BTN-3-PadP$3)") (class "Default")
      (node (ref "BTN") (pin "P$3") (pinfunction "3_P$3") (pintype "passive"))
    )
    (net (code "62") (name "unconnected-(BTN-4-PadP$4)") (class "Default")
      (node (ref "BTN") (pin "P$4") (pinfunction "4_P$4") (pintype "passive"))
    )
    (net (code "63") (name "unconnected-(RESET-3-PadP$3)") (class "Default")
      (node (ref "RESET") (pin "P$3") (pinfunction "3_P$3") (pintype "passive"))
    )
    (net (code "64") (name "unconnected-(RESET-4-PadP$4)") (class "Default")
      (node (ref "RESET") (pin "P$4") (pinfunction "4_P$4") (pintype "passive"))
    )
    (net (code "65") (name "unconnected-(U1-BP-Pad4)") (class "Default")
      (node (ref "U1") (pin "4") (pinfunction "BP_4") (pintype "input"))
    )
    (net (code "66") (name "unconnected-(U2-PadNC)") (class "Default")
      (node (ref "U2") (pin "NC") (pinfunction "NC_NC") (pintype "no_connect"))
    )
    (net (code "67") (name "unconnected-(U2-PadRESERVED_1)") (class "Default")
      (node (ref "U2") (pin "RESERVED_1") (pinfunction "RESERVED_1_RESERVED_1") (pintype "bidirectional"))
    )
    (net (code "68") (name "unconnected-(U2-PadRESERVED_2)") (class "Default")
      (node (ref "U2") (pin "RESERVED_2") (pinfunction "RESERVED_2_RESERVED_2") (pintype "bidirectional"))
    )
    (net (code "69") (name "unconnected-(U2-PadRESERVED_3)") (class "Default")
      (node (ref "U2") (pin "RESERVED_3") (pinfunction "RESERVED_3_RESERVED_3") (pintype "bidirectional"))
    )
    (net (code "70") (name "unconnected-(U3F-PC13-Pad2)") (class "Default")
      (node (ref "U3") (pin "2") (pinfunction "PC13_2") (pintype "bidirectional"))
    )
    (net (code "71") (name "unconnected-(U3F-PC14-Pad3)") (class "Default")
      (node (ref "U3") (pin "3") (pinfunction "PC14_3") (pintype "bidirectional"))
    )
    (net (code "72") (name "unconnected-(U3F-PC15-Pad4)") (class "Default")
      (node (ref "U3") (pin "4") (pinfunction "PC15_4") (pintype "bidirectional"))
    )
  )
)
